# M784bad.net
KiCad netlist of a schematic drawn in EAGLE
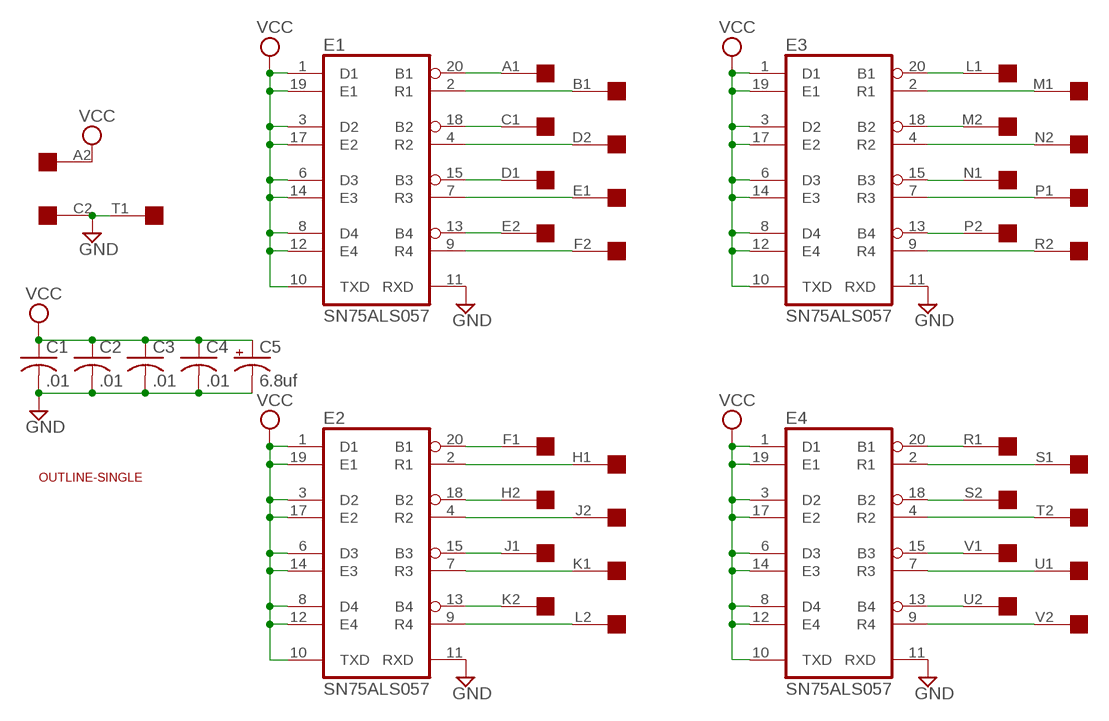
[diagram p0: schematic, sheet 1]

(export (version "E")
  (design (tool "Eeschema 10.0.6"))
  (components
    (comp (ref "C1")
      (value ".01")
      (footprint "eagle-import:C050-025X075")
      (libsource (lib "eagle-import") (part "C-US050-025X075"))
    )
    (comp (ref "C2")
      (value ".01")
      (footprint "eagle-import:C050-025X075")
      (libsource (lib "eagle-import") (part "C-US050-025X075"))
    )
    (comp (ref "C3")
      (value ".01")
      (footprint "eagle-import:C050-025X075")
      (libsource (lib "eagle-import") (part "C-US050-025X075"))
    )
    (comp (ref "C4")
      (value ".01")
      (footprint "eagle-import:C050-025X075")
      (libsource (lib "eagle-import") (part "C-US050-025X075"))
    )
    (comp (ref "C5")
      (value "6.8uf")
      (footprint "eagle-import:E15-5")
      (libsource (lib "eagle-import") (part "CPOL-USE15-5AXIAL"))
    )
    (comp (ref "E1")
      (value "SN75ALS057")
      (footprint "eagle-import:DIL20")
      (libsource (lib "eagle-import") (part "SN75ALS057"))
    )
    (comp (ref "E2")
      (value "SN75ALS057")
      (footprint "eagle-import:DIL20")
      (libsource (lib "eagle-import") (part "SN75ALS057"))
    )
    (comp (ref "E3")
      (value "SN75ALS057")
      (footprint "eagle-import:DIL20")
      (libsource (lib "eagle-import") (part "SN75ALS057"))
    )
    (comp (ref "E4")
      (value "SN75ALS057")
      (footprint "eagle-import:DIL20")
      (libsource (lib "eagle-import") (part "SN75ALS057"))
    )
    (comp (ref "U$1")
      (value "SINGLE")
      (footprint "eagle-import:EDGE-CON2")
      (libsource (lib "eagle-import") (part "SINGLE"))
    )
    (comp (ref "U$2")
      (value "OUTLINE-SINGLE")
      (footprint "eagle-import:SINGLE")
      (libsource (lib "eagle-import") (part "OUTLINE-SINGLE"))
    )
  )
  (nets
    (net (code "1") (name "GND") (class "Default")
      (node (ref "C1") (pin "2") (pinfunction "2_2") (pintype "passive"))
      (node (ref "C2") (pin "2") (pinfunction "2_2") (pintype "passive"))
      (node (ref "C3") (pin "2") (pinfunction "2_2") (pintype "passive"))
      (node (ref "C4") (pin "2") (pinfunction "2_2") (pintype "passive"))
      (node (ref "C5") (pin "-") (pinfunction "-_-") (pintype "passive"))
      (node (ref "E1") (pin "11") (pinfunction "RXD_11") (pintype "input"))
      (node (ref "E2") (pin "11") (pinfunction "RXD_11") (pintype "input"))
      (node (ref "E3") (pin "11") (pinfunction "RXD_11") (pintype "input"))
      (node (ref "E4") (pin "11") (pinfunction "RXD_11") (pintype "input"))
      (node (ref "U$1") (pin "C2") (pinfunction "1_C2") (pintype "bidirectional"))
      (node (ref "U$1") (pin "T1") (pinfunction "1_T1") (pintype "bidirectional"))
    )
    (net (code "2") (name "Net-(E1A-B1)") (class "Default")
      (node (ref "E1") (pin "20") (pinfunction "B1_20") (pintype "bidirectional"))
      (node (ref "U$1") (pin "A1") (pinfunction "1_A1") (pintype "bidirectional"))
    )
    (net (code "3") (name "Net-(E1A-B2)") (class "Default")
      (node (ref "E1") (pin "18") (pinfunction "B2_18") (pintype "bidirectional"))
      (node (ref "U$1") (pin "C1") (pinfunction "1_C1") (pintype "bidirectional"))
    )
    (net (code "4") (name "Net-(E1A-B3)") (class "Default")
      (node (ref "E1") (pin "15") (pinfunction "B3_15") (pintype "bidirectional"))
      (node (ref "U$1") (pin "D1") (pinfunction "1_D1") (pintype "bidirectional"))
    )
    (net (code "5") (name "Net-(E1A-B4)") (class "Default")
      (node (ref "E1") (pin "13") (pinfunction "B4_13") (pintype "bidirectional"))
      (node (ref "U$1") (pin "E2") (pinfunction "1_E2") (pintype "bidirectional"))
    )
    (net (code "6") (name "Net-(E1A-R1)") (class "Default")
      (node (ref "E1") (pin "2") (pinfunction "R1_2") (pintype "output"))
      (node (ref "U$1") (pin "B1") (pinfunction "1_B1") (pintype "bidirectional"))
    )
    (net (code "7") (name "Net-(E1A-R2)") (class "Default")
      (node (ref "E1") (pin "4") (pinfunction "R2_4") (pintype "output"))
      (node (ref "U$1") (pin "D2") (pinfunction "1_D2") (pintype "bidirectional"))
    )
    (net (code "8") (name "Net-(E1A-R3)") (class "Default")
      (node (ref "E1") (pin "7") (pinfunction "R3_7") (pintype "output"))
      (node (ref "U$1") (pin "E1") (pinfunction "1_E1") (pintype "bidirectional"))
    )
    (net (code "9") (name "Net-(E1A-R4)") (class "Default")
      (node (ref "E1") (pin "9") (pinfunction "R4_9") (pintype "output"))
      (node (ref "U$1") (pin "F2") (pinfunction "1_F2") (pintype "bidirectional"))
    )
    (net (code "10") (name "Net-(E2A-B1)") (class "Default")
      (node (ref "E2") (pin "20") (pinfunction "B1_20") (pintype "bidirectional"))
      (node (ref "U$1") (pin "F1") (pinfunction "1_F1") (pintype "bidirectional"))
    )
    (net (code "11") (name "Net-(E2A-B2)") (class "Default")
      (node (ref "E2") (pin "18") (pinfunction "B2_18") (pintype "bidirectional"))
      (node (ref "U$1") (pin "H2") (pinfunction "1_H2") (pintype "bidirectional"))
    )
    (net (code "12") (name "Net-(E2A-B3)") (class "Default")
      (node (ref "E2") (pin "15") (pinfunction "B3_15") (pintype "bidirectional"))
      (node (ref "U$1") (pin "J1") (pinfunction "1_J1") (pintype "bidirectional"))
    )
    (net (code "13") (name "Net-(E2A-B4)") (class "Default")
      (node (ref "E2") (pin "13") (pinfunction "B4_13") (pintype "bidirectional"))
      (node (ref "U$1") (pin "K2") (pinfunction "1_K2") (pintype "bidirectional"))
    )
    (net (code "14") (name "Net-(E2A-R1)") (class "Default")
      (node (ref "E2") (pin "2") (pinfunction "R1_2") (pintype "output"))
      (node (ref "U$1") (pin "H1") (pinfunction "1_H1") (pintype "bidirectional"))
    )
    (net (code "15") (name "Net-(E2A-R2)") (class "Default")
      (node (ref "E2") (pin "4") (pinfunction "R2_4") (pintype "output"))
      (node (ref "U$1") (pin "J2") (pinfunction "1_J2") (pintype "bidirectional"))
    )
    (net (code "16") (name "Net-(E2A-R3)") (class "Default")
      (node (ref "E2") (pin "7") (pinfunction "R3_7") (pintype "output"))
      (node (ref "U$1") (pin "K1") (pinfunction "1_K1") (pintype "bidirectional"))
    )
    (net (code "17") (name "Net-(E2A-R4)") (class "Default")
      (node (ref "E2") (pin "9") (pinfunction "R4_9") (pintype "output"))
      (node (ref "U$1") (pin "L2") (pinfunction "1_L2") (pintype "bidirectional"))
    )
    (net (code "18") (name "Net-(E3A-B1)") (class "Default")
      (node (ref "E3") (pin "20") (pinfunction "B1_20") (pintype "bidirectional"))
      (node (ref "U$1") (pin "L1") (pinfunction "1_L1") (pintype "bidirectional"))
    )
    (net (code "19") (name "Net-(E3A-B2)") (class "Default")
      (node (ref "E3") (pin "18") (pinfunction "B2_18") (pintype "bidirectional"))
      (node (ref "U$1") (pin "M2") (pinfunction "1_M2") (pintype "bidirectional"))
    )
    (net (code "20") (name "Net-(E3A-B3)") (class "Default")
      (node (ref "E3") (pin "15") (pinfunction "B3_15") (pintype "bidirectional"))
      (node (ref "U$1") (pin "N1") (pinfunction "1_N1") (pintype "bidirectional"))
    )
    (net (code "21") (name "Net-(E3A-B4)") (class "Default")
      (node (ref "E3") (pin "13") (pinfunction "B4_13") (pintype "bidirectional"))
      (node (ref "U$1") (pin "P2") (pinfunction "1_P2") (pintype "bidirectional"))
    )
    (net (code "22") (name "Net-(E3A-R1)") (class "Default")
      (node (ref "E3") (pin "2") (pinfunction "R1_2") (pintype "output"))
      (node (ref "U$1") (pin "M1") (pinfunction "1_M1") (pintype "bidirectional"))
    )
    (net (code "23") (name "Net-(E3A-R2)") (class "Default")
      (node (ref "E3") (pin "4") (pinfunction "R2_4") (pintype "output"))
      (node (ref "U$1") (pin "N2") (pinfunction "1_N2") (pintype "bidirectional"))
    )
    (net (code "24") (name "Net-(E3A-R3)") (class "Default")
      (node (ref "E3") (pin "7") (pinfunction "R3_7") (pintype "output"))
      (node (ref "U$1") (pin "P1") (pinfunction "1_P1") (pintype "bidirectional"))
    )
    (net (code "25") (name "Net-(E3A-R4)") (class "Default")
      (node (ref "E3") (pin "9") (pinfunction "R4_9") (pintype "output"))
      (node (ref "U$1") (pin "R2") (pinfunction "1_R2") (pintype "bidirectional"))
    )
    (net (code "26") (name "Net-(E4A-B1)") (class "Default")
      (node (ref "E4") (pin "20") (pinfunction "B1_20") (pintype "bidirectional"))
      (node (ref "U$1") (pin "R1") (pinfunction "1_R1") (pintype "bidirectional"))
    )
    (net (code "27") (name "Net-(E4A-B2)") (class "Default")
      (node (ref "E4") (pin "18") (pinfunction "B2_18") (pintype "bidirectional"))
      (node (ref "U$1") (pin "S2") (pinfunction "1_S2") (pintype "bidirectional"))
    )
    (net (code "28") (name "Net-(E4A-B3)") (class "Default")
      (node (ref "E4") (pin "15") (pinfunction "B3_15") (pintype "bidirectional"))
      (node (ref "U$1") (pin "V1") (pinfunction "1_V1") (pintype "bidirectional"))
    )
    (net (code "29") (name "Net-(E4A-B4)") (class "Default")
      (node (ref "E4") (pin "13") (pinfunction "B4_13") (pintype "bidirectional"))
      (node (ref "U$1") (pin "U2") (pinfunction "1_U2") (pintype "bidirectional"))
    )
    (net (code "30") (name "Net-(E4A-R1)") (class "Default")
      (node (ref "E4") (pin "2") (pinfunction "R1_2") (pintype "output"))
      (node (ref "U$1") (pin "S1") (pinfunction "1_S1") (pintype "bidirectional"))
    )
    (net (code "31") (name "Net-(E4A-R2)") (class "Default")
      (node (ref "E4") (pin "4") (pinfunction "R2_4") (pintype "output"))
      (node (ref "U$1") (pin "T2") (pinfunction "1_T2") (pintype "bidirectional"))
    )
    (net (code "32") (name "Net-(E4A-R3)") (class "Default")
      (node (ref "E4") (pin "7") (pinfunction "R3_7") (pintype "output"))
      (node (ref "U$1") (pin "U1") (pinfunction "1_U1") (pintype "bidirectional"))
    )
    (net (code "33") (name "Net-(E4A-R4)") (class "Default")
      (node (ref "E4") (pin "9") (pinfunction "R4_9") (pintype "output"))
      (node (ref "U$1") (pin "V2") (pinfunction "1_V2") (pintype "bidirectional"))
    )
    (net (code "34") (name "VCC") (class "Default")
      (node (ref "C1") (pin "1") (pinfunction "1_1") (pintype "passive"))
      (node (ref "C2") (pin "1") (pinfunction "1_1") (pintype "passive"))
      (node (ref "C3") (pin "1") (pinfunction "1_1") (pintype "passive"))
      (node (ref "C4") (pin "1") (pinfunction "1_1") (pintype "passive"))
      (node (ref "C5") (pin "+") (pinfunction "+_+") (pintype "passive"))
      (node (ref "E1") (pin "1") (pinfunction "D1_1") (pintype "input"))
      (node (ref "E1") (pin "10") (pinfunction "TXD_10") (pintype "input"))
      (node (ref "E1") (pin "12") (pinfunction "E4_12") (pintype "input"))
      (node (ref "E1") (pin "14") (pinfunction "E3_14") (pintype "input"))
      (node (ref "E1") (pin "17") (pinfunction "E2_17") (pintype "input"))
      (node (ref "E1") (pin "19") (pinfunction "E1_19") (pintype "input"))
      (node (ref "E1") (pin "3") (pinfunction "D2_3") (pintype "input"))
      (node (ref "E1") (pin "6") (pinfunction "D3_6") (pintype "input"))
      (node (ref "E1") (pin "8") (pinfunction "D4_8") (pintype "input"))
      (node (ref "E2") (pin "1") (pinfunction "D1_1") (pintype "input"))
      (node (ref "E2") (pin "10") (pinfunction "TXD_10") (pintype "input"))
      (node (ref "E2") (pin "12") (pinfunction "E4_12") (pintype "input"))
      (node (ref "E2") (pin "14") (pinfunction "E3_14") (pintype "input"))
      (node (ref "E2") (pin "17") (pinfunction "E2_17") (pintype "input"))
      (node (ref "E2") (pin "19") (pinfunction "E1_19") (pintype "input"))
      (node (ref "E2") (pin "3") (pinfunction "D2_3") (pintype "input"))
      (node (ref "E2") (pin "6") (pinfunction "D3_6") (pintype "input"))
      (node (ref "E2") (pin "8") (pinfunction "D4_8") (pintype "input"))
      (node (ref "E3") (pin "1") (pinfunction "D1_1") (pintype "input"))
      (node (ref "E3") (pin "10") (pinfunction "TXD_10") (pintype "input"))
      (node (ref "E3") (pin "12") (pinfunction "E4_12") (pintype "input"))
      (node (ref "E3") (pin "14") (pinfunction "E3_14") (pintype "input"))
      (node (ref "E3") (pin "17") (pinfunction "E2_17") (pintype "input"))
      (node (ref "E3") (pin "19") (pinfunction "E1_19") (pintype "input"))
      (node (ref "E3") (pin "3") (pinfunction "D2_3") (pintype "input"))
      (node (ref "E3") (pin "6") (pinfunction "D3_6") (pintype "input"))
      (node (ref "E3") (pin "8") (pinfunction "D4_8") (pintype "input"))
      (node (ref "E4") (pin "1") (pinfunction "D1_1") (pintype "input"))
      (node (ref "E4") (pin "10") (pinfunction "TXD_10") (pintype "input"))
      (node (ref "E4") (pin "12") (pinfunction "E4_12") (pintype "input"))
      (node (ref "E4") (pin "14") (pinfunction "E3_14") (pintype "input"))
      (node (ref "E4") (pin "17") (pinfunction "E2_17") (pintype "input"))
      (node (ref "E4") (pin "19") (pinfunction "E1_19") (pintype "input"))
      (node (ref "E4") (pin "3") (pinfunction "D2_3") (pintype "input"))
      (node (ref "E4") (pin "6") (pinfunction "D3_6") (pintype "input"))
      (node (ref "E4") (pin "8") (pinfunction "D4_8") (pintype "input"))
      (node (ref "U$1") (pin "A2") (pinfunction "1_A2") (pintype "bidirectional"))
    )
  )
)
